# hump.net
KiCad netlist of a schematic drawn in EAGLE
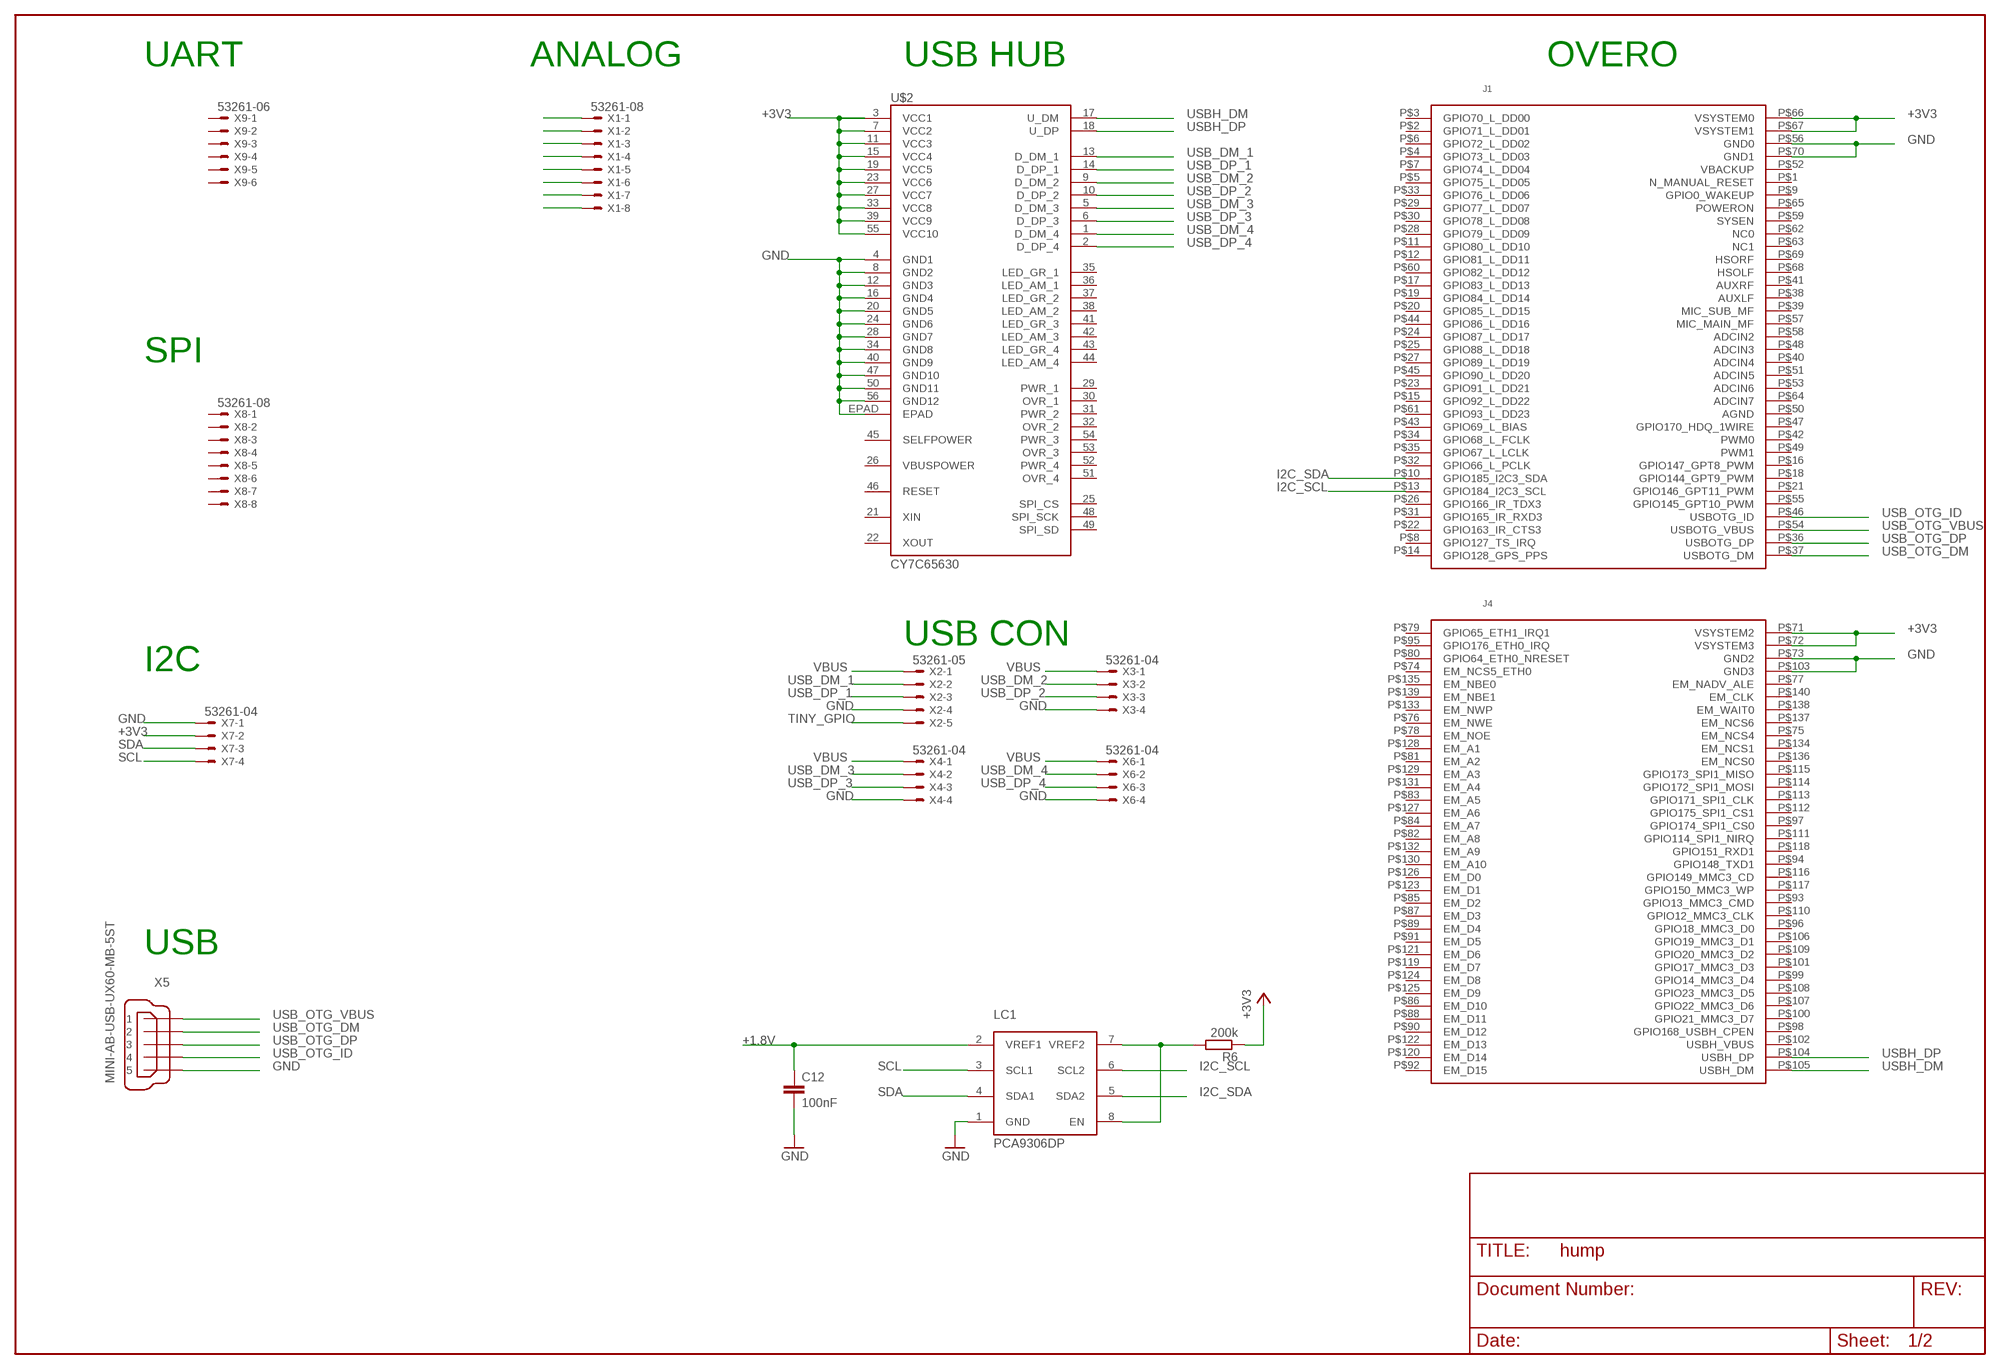
[diagram p0: schematic, sheet 1]
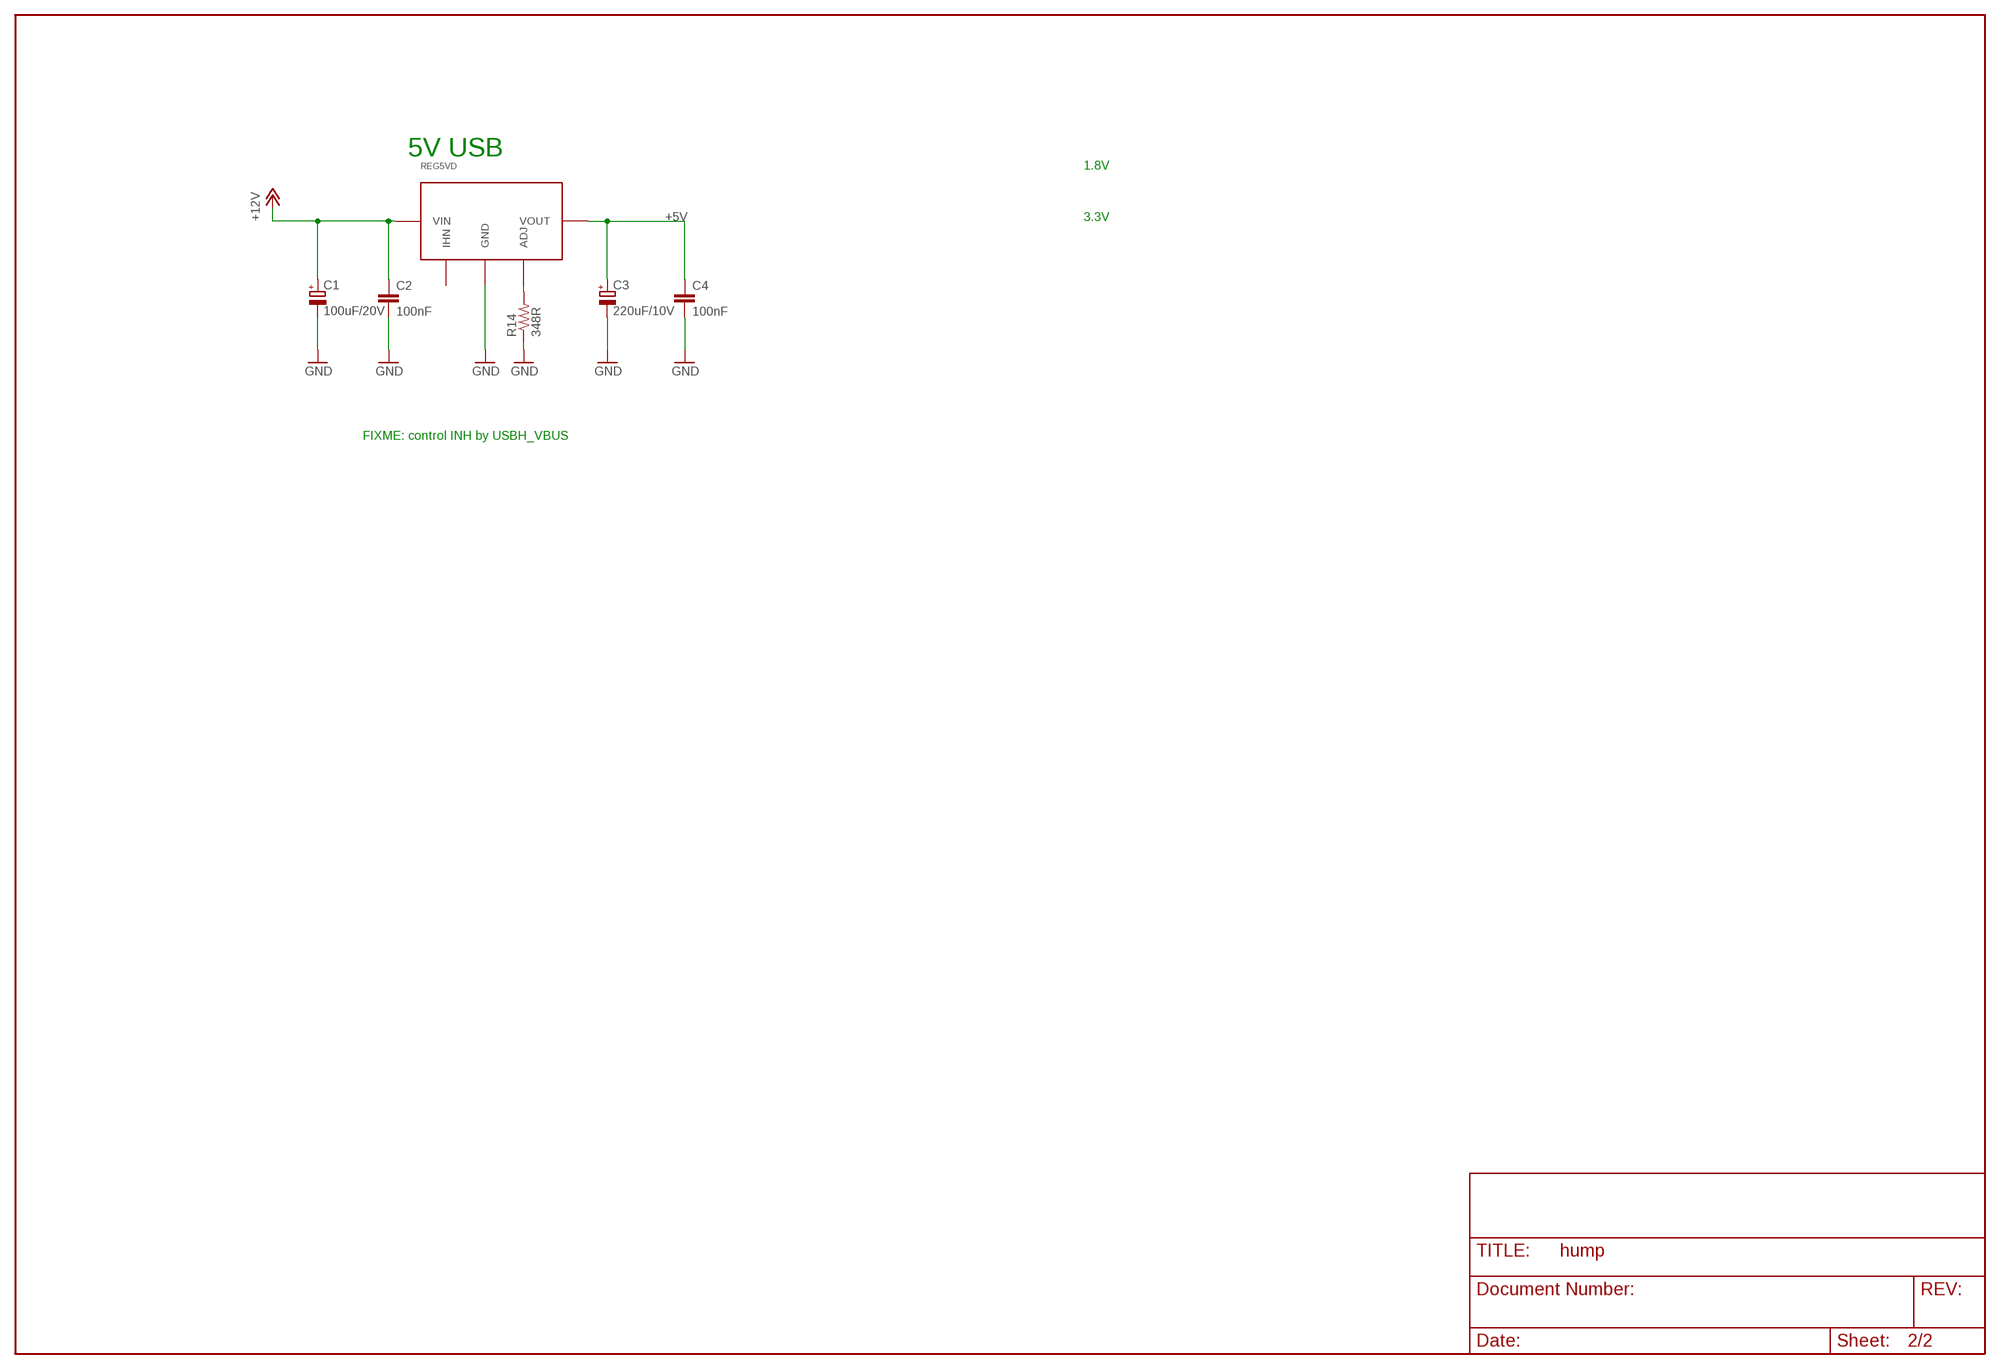
[diagram p1: schematic, sheet 2]

(export (version "E")
  (design (tool "Eeschema 10.0.6"))
  (components
    (comp (ref "C12")
      (value "100nF")
      (footprint "eagle-import:C0603")
      (libsource (lib "eagle-import") (part "C-EUC0603"))
    )
    (comp (ref "LC1")
      (value "PCA9306DP")
      (footprint "eagle-import:TSSOP_B3")
      (libsource (lib "eagle-import") (part "PCA9306DP"))
    )
    (comp (ref "R6")
      (value "200k")
      (footprint "eagle-import:R0603")
      (libsource (lib "eagle-import") (part "R-EU_R0603"))
    )
    (comp (ref "U$1")
      (value "CON_OVERO")
      (footprint "eagle-import:CON_OVERO")
      (libsource (lib "eagle-import") (part "CON_OVERO"))
    )
    (comp (ref "U$2")
      (value "CY7C65630")
      (footprint "eagle-import:QFN56")
      (libsource (lib "eagle-import") (part "CY7C65630"))
    )
    (comp (ref "X1")
      (value "53261-08")
      (footprint "eagle-import:53261-08")
      (libsource (lib "eagle-import") (part "53?-08261"))
    )
    (comp (ref "X2")
      (value "53261-05")
      (footprint "eagle-import:53261-05")
      (libsource (lib "eagle-import") (part "53?-05261"))
    )
    (comp (ref "X3")
      (value "53261-04")
      (footprint "eagle-import:53261-04")
      (libsource (lib "eagle-import") (part "53?-04261"))
    )
    (comp (ref "X4")
      (value "53261-04")
      (footprint "eagle-import:53261-04")
      (libsource (lib "eagle-import") (part "53?-04261"))
    )
    (comp (ref "X5")
      (value "MINI-AB-USB-UX60-MB-5ST")
      (footprint "eagle-import:UX60-MB-5ST")
      (libsource (lib "eagle-import") (part "MINI-USB-UX60-MB-5ST"))
    )
    (comp (ref "X6")
      (value "53261-04")
      (footprint "eagle-import:53261-04")
      (libsource (lib "eagle-import") (part "53?-04261"))
    )
    (comp (ref "X7")
      (value "53261-04")
      (footprint "eagle-import:53261-04")
      (libsource (lib "eagle-import") (part "53?-04261"))
    )
    (comp (ref "X8")
      (value "53261-08")
      (footprint "eagle-import:53261-08")
      (libsource (lib "eagle-import") (part "53?-08261"))
    )
    (comp (ref "X9")
      (value "53261-06")
      (footprint "eagle-import:53261-06")
      (libsource (lib "eagle-import") (part "53?-06261"))
    )
    (comp (ref "C1")
      (value "100uF/20V")
      (footprint "eagle-import:SMC_D")
      (libsource (lib "eagle-import") (part "CPOL-EUSMCD"))
    )
    (comp (ref "C2")
      (value "100nF")
      (footprint "eagle-import:C0603")
      (libsource (lib "eagle-import") (part "C-EUC0603"))
    )
    (comp (ref "C3")
      (value "220uF/10V")
      (footprint "eagle-import:SMC_D")
      (libsource (lib "eagle-import") (part "CPOL-EUSMCD"))
    )
    (comp (ref "C4")
      (value "100nF")
      (footprint "eagle-import:C0603")
      (libsource (lib "eagle-import") (part "C-EUC0603"))
    )
    (comp (ref "R14")
      (value "348R")
      (footprint "eagle-import:R0603")
      (libsource (lib "eagle-import") (part "R-US_R0603"))
    )
    (comp (ref "REG5VD")
      (value "PTHTH")
      (footprint "eagle-import:PTH_TH")
      (libsource (lib "eagle-import") (part "PTHTH"))
    )
  )
  (nets
    (net (code "1") (name "+1.8V") (class "Default")
      (node (ref "C12") (pin "1") (pinfunction "1_1") (pintype "passive"))
      (node (ref "LC1") (pin "2") (pinfunction "VREF1_2") (pintype "bidirectional"))
    )
    (net (code "2") (name "+3V3") (class "Default")
      (node (ref "R6") (pin "1") (pinfunction "1_1") (pintype "passive"))
      (node (ref "U$1") (pin "P$66") (pinfunction "VSYSTEM0_P$66") (pintype "bidirectional"))
      (node (ref "U$1") (pin "P$67") (pinfunction "VSYSTEM1_P$67") (pintype "bidirectional"))
      (node (ref "U$1") (pin "P$71") (pinfunction "VSYSTEM2_P$71") (pintype "bidirectional"))
      (node (ref "U$1") (pin "P$72") (pinfunction "VSYSTEM3_P$72") (pintype "bidirectional"))
      (node (ref "U$2") (pin "11") (pinfunction "VCC3_11") (pintype "power_in"))
      (node (ref "U$2") (pin "15") (pinfunction "VCC4_15") (pintype "power_in"))
      (node (ref "U$2") (pin "19") (pinfunction "VCC5_19") (pintype "power_in"))
      (node (ref "U$2") (pin "23") (pinfunction "VCC6_23") (pintype "power_in"))
      (node (ref "U$2") (pin "27") (pinfunction "VCC7_27") (pintype "power_in"))
      (node (ref "U$2") (pin "3") (pinfunction "VCC1_3") (pintype "power_in"))
      (node (ref "U$2") (pin "33") (pinfunction "VCC8_33") (pintype "power_in"))
      (node (ref "U$2") (pin "39") (pinfunction "VCC9_39") (pintype "power_in"))
      (node (ref "U$2") (pin "55") (pinfunction "VCC10_55") (pintype "power_in"))
      (node (ref "U$2") (pin "7") (pinfunction "VCC2_7") (pintype "power_in"))
      (node (ref "X7") (pin "2") (pinfunction "S_2") (pintype "passive"))
    )
    (net (code "3") (name "+5V") (class "Default")
      (node (ref "C3") (pin "+") (pinfunction "+_+") (pintype "passive"))
      (node (ref "C4") (pin "1") (pinfunction "1_1") (pintype "passive"))
      (node (ref "REG5VD") (pin "P$3") (pinfunction "VOUT_P$3") (pintype "bidirectional"))
    )
    (net (code "4") (name "+12V") (class "Default")
      (node (ref "C1") (pin "+") (pinfunction "+_+") (pintype "passive"))
      (node (ref "C2") (pin "1") (pinfunction "1_1") (pintype "passive"))
      (node (ref "REG5VD") (pin "P$1") (pinfunction "VIN_P$1") (pintype "bidirectional"))
    )
    (net (code "5") (name "GND") (class "Default")
      (node (ref "C1") (pin "-") (pinfunction "-_-") (pintype "passive"))
      (node (ref "C12") (pin "2") (pinfunction "2_2") (pintype "passive"))
      (node (ref "C2") (pin "2") (pinfunction "2_2") (pintype "passive"))
      (node (ref "C3") (pin "-") (pinfunction "-_-") (pintype "passive"))
      (node (ref "C4") (pin "2") (pinfunction "2_2") (pintype "passive"))
      (node (ref "LC1") (pin "1") (pinfunction "GND_1") (pintype "bidirectional"))
      (node (ref "R14") (pin "1") (pinfunction "1_1") (pintype "passive"))
      (node (ref "REG5VD") (pin "P$2") (pinfunction "GND_P$2") (pintype "bidirectional"))
      (node (ref "U$1") (pin "P$103") (pinfunction "GND3_P$103") (pintype "bidirectional"))
      (node (ref "U$1") (pin "P$56") (pinfunction "GND0_P$56") (pintype "bidirectional"))
      (node (ref "U$1") (pin "P$70") (pinfunction "GND1_P$70") (pintype "bidirectional"))
      (node (ref "U$1") (pin "P$73") (pinfunction "GND2_P$73") (pintype "bidirectional"))
      (node (ref "U$2") (pin "12") (pinfunction "GND3_12") (pintype "power_in"))
      (node (ref "U$2") (pin "16") (pinfunction "GND4_16") (pintype "power_in"))
      (node (ref "U$2") (pin "20") (pinfunction "GND5_20") (pintype "power_in"))
      (node (ref "U$2") (pin "24") (pinfunction "GND6_24") (pintype "power_in"))
      (node (ref "U$2") (pin "28") (pinfunction "GND7_28") (pintype "power_in"))
      (node (ref "U$2") (pin "34") (pinfunction "GND8_34") (pintype "power_in"))
      (node (ref "U$2") (pin "4") (pinfunction "GND1_4") (pintype "power_in"))
      (node (ref "U$2") (pin "40") (pinfunction "GND9_40") (pintype "power_in"))
      (node (ref "U$2") (pin "47") (pinfunction "GND10_47") (pintype "power_in"))
      (node (ref "U$2") (pin "50") (pinfunction "GND11_50") (pintype "power_in"))
      (node (ref "U$2") (pin "56") (pinfunction "GND12_56") (pintype "power_in"))
      (node (ref "U$2") (pin "8") (pinfunction "GND2_8") (pintype "power_in"))
      (node (ref "U$2") (pin "EPAD") (pinfunction "EPAD_EPAD") (pintype "power_in"))
      (node (ref "X1") (pin "1") (pinfunction "S_1") (pintype "passive"))
      (node (ref "X2") (pin "4") (pinfunction "S_4") (pintype "passive"))
      (node (ref "X3") (pin "4") (pinfunction "S_4") (pintype "passive"))
      (node (ref "X4") (pin "4") (pinfunction "S_4") (pintype "passive"))
      (node (ref "X5") (pin "5") (pinfunction "5_5") (pintype "input"))
      (node (ref "X6") (pin "4") (pinfunction "S_4") (pintype "passive"))
      (node (ref "X7") (pin "1") (pinfunction "S_1") (pintype "passive"))
    )
    (net (code "6") (name "I2C_SCL") (class "Default")
      (node (ref "LC1") (pin "6") (pinfunction "SCL2_6") (pintype "bidirectional"))
      (node (ref "U$1") (pin "P$13") (pinfunction "GPIO184_I2C3_SCL_P$13") (pintype "bidirectional"))
    )
    (net (code "7") (name "I2C_SDA") (class "Default")
      (node (ref "LC1") (pin "5") (pinfunction "SDA2_5") (pintype "bidirectional"))
      (node (ref "U$1") (pin "P$10") (pinfunction "GPIO185_I2C3_SDA_P$10") (pintype "bidirectional"))
    )
    (net (code "8") (name "Net-(LC1-EN)") (class "Default")
      (node (ref "LC1") (pin "7") (pinfunction "VREF2_7") (pintype "bidirectional"))
      (node (ref "LC1") (pin "8") (pinfunction "EN_8") (pintype "bidirectional"))
      (node (ref "R6") (pin "2") (pinfunction "2_2") (pintype "passive"))
    )
    (net (code "9") (name "Net-(REG5VD-ADJ)") (class "Default")
      (node (ref "R14") (pin "2") (pinfunction "2_2") (pintype "passive"))
      (node (ref "REG5VD") (pin "P$4") (pinfunction "ADJ_P$4") (pintype "bidirectional"))
    )
    (net (code "10") (name "SCL") (class "Default")
      (node (ref "LC1") (pin "3") (pinfunction "SCL1_3") (pintype "bidirectional"))
      (node (ref "X7") (pin "4") (pinfunction "S_4") (pintype "passive"))
    )
    (net (code "11") (name "SDA") (class "Default")
      (node (ref "LC1") (pin "4") (pinfunction "SDA1_4") (pintype "bidirectional"))
      (node (ref "X7") (pin "3") (pinfunction "S_3") (pintype "passive"))
    )
    (net (code "12") (name "TINY_GPIO") (class "Default")
      (node (ref "X2") (pin "5") (pinfunction "S_5") (pintype "passive"))
    )
    (net (code "13") (name "USBH_DM") (class "Default")
      (node (ref "U$1") (pin "P$105") (pinfunction "USBH_DM_P$105") (pintype "bidirectional"))
      (node (ref "U$2") (pin "17") (pinfunction "U_DM_17") (pintype "bidirectional"))
    )
    (net (code "14") (name "USBH_DP") (class "Default")
      (node (ref "U$1") (pin "P$104") (pinfunction "USBH_DP_P$104") (pintype "bidirectional"))
      (node (ref "U$2") (pin "18") (pinfunction "U_DP_18") (pintype "bidirectional"))
    )
    (net (code "15") (name "USB_DM_1") (class "Default")
      (node (ref "U$2") (pin "13") (pinfunction "D_DM_1_13") (pintype "bidirectional"))
      (node (ref "X2") (pin "2") (pinfunction "S_2") (pintype "passive"))
    )
    (net (code "16") (name "USB_DM_2") (class "Default")
      (node (ref "U$2") (pin "9") (pinfunction "D_DM_2_9") (pintype "bidirectional"))
      (node (ref "X3") (pin "2") (pinfunction "S_2") (pintype "passive"))
    )
    (net (code "17") (name "USB_DM_3") (class "Default")
      (node (ref "U$2") (pin "5") (pinfunction "D_DM_3_5") (pintype "bidirectional"))
      (node (ref "X4") (pin "2") (pinfunction "S_2") (pintype "passive"))
    )
    (net (code "18") (name "USB_DM_4") (class "Default")
      (node (ref "U$2") (pin "1") (pinfunction "D_DM_4_1") (pintype "bidirectional"))
      (node (ref "X6") (pin "2") (pinfunction "S_2") (pintype "passive"))
    )
    (net (code "19") (name "USB_DP_1") (class "Default")
      (node (ref "U$2") (pin "14") (pinfunction "D_DP_1_14") (pintype "bidirectional"))
      (node (ref "X2") (pin "3") (pinfunction "S_3") (pintype "passive"))
    )
    (net (code "20") (name "USB_DP_2") (class "Default")
      (node (ref "U$2") (pin "10") (pinfunction "D_DP_2_10") (pintype "bidirectional"))
      (node (ref "X3") (pin "3") (pinfunction "S_3") (pintype "passive"))
    )
    (net (code "21") (name "USB_DP_3") (class "Default")
      (node (ref "U$2") (pin "6") (pinfunction "D_DP_3_6") (pintype "bidirectional"))
      (node (ref "X4") (pin "3") (pinfunction "S_3") (pintype "passive"))
    )
    (net (code "22") (name "USB_DP_4") (class "Default")
      (node (ref "U$2") (pin "2") (pinfunction "D_DP_4_2") (pintype "bidirectional"))
      (node (ref "X6") (pin "3") (pinfunction "S_3") (pintype "passive"))
    )
    (net (code "23") (name "USB_OTG_DM") (class "Default")
      (node (ref "U$1") (pin "P$37") (pinfunction "USBOTG_DM_P$37") (pintype "bidirectional"))
      (node (ref "X5") (pin "2") (pinfunction "2_2") (pintype "input"))
    )
    (net (code "24") (name "USB_OTG_DP") (class "Default")
      (node (ref "U$1") (pin "P$36") (pinfunction "USBOTG_DP_P$36") (pintype "bidirectional"))
      (node (ref "X5") (pin "3") (pinfunction "3_3") (pintype "input"))
    )
    (net (code "25") (name "USB_OTG_ID") (class "Default")
      (node (ref "U$1") (pin "P$46") (pinfunction "USBOTG_ID_P$46") (pintype "bidirectional"))
      (node (ref "X5") (pin "4") (pinfunction "4_4") (pintype "input"))
    )
    (net (code "26") (name "USB_OTG_VBUS") (class "Default")
      (node (ref "U$1") (pin "P$54") (pinfunction "USBOTG_VBUS_P$54") (pintype "bidirectional"))
      (node (ref "X5") (pin "1") (pinfunction "1_1") (pintype "input"))
    )
    (net (code "27") (name "VBUS") (class "Default")
      (node (ref "X2") (pin "1") (pinfunction "S_1") (pintype "passive"))
      (node (ref "X3") (pin "1") (pinfunction "S_1") (pintype "passive"))
      (node (ref "X4") (pin "1") (pinfunction "S_1") (pintype "passive"))
      (node (ref "X6") (pin "1") (pinfunction "S_1") (pintype "passive"))
    )
    (net (code "28") (name "unconnected-(REG5VD-IHN-PadP$5)") (class "Default")
      (node (ref "REG5VD") (pin "P$5") (pinfunction "IHN_P$5") (pintype "bidirectional"))
    )
    (net (code "29") (name "unconnected-(U$1-ADCIN2-PadP$58)") (class "Default")
      (node (ref "U$1") (pin "P$58") (pinfunction "ADCIN2_P$58") (pintype "bidirectional"))
    )
    (net (code "30") (name "unconnected-(U$1-ADCIN3-PadP$48)") (class "Default")
      (node (ref "U$1") (pin "P$48") (pinfunction "ADCIN3_P$48") (pintype "bidirectional"))
    )
    (net (code "31") (name "unconnected-(U$1-ADCIN4-PadP$40)") (class "Default")
      (node (ref "U$1") (pin "P$40") (pinfunction "ADCIN4_P$40") (pintype "bidirectional"))
    )
    (net (code "32") (name "unconnected-(U$1-ADCIN5-PadP$51)") (class "Default")
      (node (ref "U$1") (pin "P$51") (pinfunction "ADCIN5_P$51") (pintype "bidirectional"))
    )
    (net (code "33") (name "unconnected-(U$1-ADCIN6-PadP$53)") (class "Default")
      (node (ref "U$1") (pin "P$53") (pinfunction "ADCIN6_P$53") (pintype "bidirectional"))
    )
    (net (code "34") (name "unconnected-(U$1-ADCIN7-PadP$64)") (class "Default")
      (node (ref "U$1") (pin "P$64") (pinfunction "ADCIN7_P$64") (pintype "bidirectional"))
    )
    (net (code "35") (name "unconnected-(U$1-AGND-PadP$50)") (class "Default")
      (node (ref "U$1") (pin "P$50") (pinfunction "AGND_P$50") (pintype "bidirectional"))
    )
    (net (code "36") (name "unconnected-(U$1-AUXLF-PadP$38)") (class "Default")
      (node (ref "U$1") (pin "P$38") (pinfunction "AUXLF_P$38") (pintype "bidirectional"))
    )
    (net (code "37") (name "unconnected-(U$1-AUXRF-PadP$41)") (class "Default")
      (node (ref "U$1") (pin "P$41") (pinfunction "AUXRF_P$41") (pintype "bidirectional"))
    )
    (net (code "38") (name "unconnected-(U$1-EM_A1-PadP$128)") (class "Default")
      (node (ref "U$1") (pin "P$128") (pinfunction "EM_A1_P$128") (pintype "bidirectional"))
    )
    (net (code "39") (name "unconnected-(U$1-EM_A2-PadP$81)") (class "Default")
      (node (ref "U$1") (pin "P$81") (pinfunction "EM_A2_P$81") (pintype "bidirectional"))
    )
    (net (code "40") (name "unconnected-(U$1-EM_A3-PadP$129)") (class "Default")
      (node (ref "U$1") (pin "P$129") (pinfunction "EM_A3_P$129") (pintype "bidirectional"))
    )
    (net (code "41") (name "unconnected-(U$1-EM_A4-PadP$131)") (class "Default")
      (node (ref "U$1") (pin "P$131") (pinfunction "EM_A4_P$131") (pintype "bidirectional"))
    )
    (net (code "42") (name "unconnected-(U$1-EM_A5-PadP$83)") (class "Default")
      (node (ref "U$1") (pin "P$83") (pinfunction "EM_A5_P$83") (pintype "bidirectional"))
    )
    (net (code "43") (name "unconnected-(U$1-EM_A6-PadP$127)") (class "Default")
      (node (ref "U$1") (pin "P$127") (pinfunction "EM_A6_P$127") (pintype "bidirectional"))
    )
    (net (code "44") (name "unconnected-(U$1-EM_A7-PadP$84)") (class "Default")
      (node (ref "U$1") (pin "P$84") (pinfunction "EM_A7_P$84") (pintype "bidirectional"))
    )
    (net (code "45") (name "unconnected-(U$1-EM_A8-PadP$82)") (class "Default")
      (node (ref "U$1") (pin "P$82") (pinfunction "EM_A8_P$82") (pintype "bidirectional"))
    )
    (net (code "46") (name "unconnected-(U$1-EM_A9-PadP$132)") (class "Default")
      (node (ref "U$1") (pin "P$132") (pinfunction "EM_A9_P$132") (pintype "bidirectional"))
    )
    (net (code "47") (name "unconnected-(U$1-EM_A10-PadP$130)") (class "Default")
      (node (ref "U$1") (pin "P$130") (pinfunction "EM_A10_P$130") (pintype "bidirectional"))
    )
    (net (code "48") (name "unconnected-(U$1-EM_CLK-PadP$140)") (class "Default")
      (node (ref "U$1") (pin "P$140") (pinfunction "EM_CLK_P$140") (pintype "bidirectional"))
    )
    (net (code "49") (name "unconnected-(U$1-EM_D0-PadP$126)") (class "Default")
      (node (ref "U$1") (pin "P$126") (pinfunction "EM_D0_P$126") (pintype "bidirectional"))
    )
    (net (code "50") (name "unconnected-(U$1-EM_D1-PadP$123)") (class "Default")
      (node (ref "U$1") (pin "P$123") (pinfunction "EM_D1_P$123") (pintype "bidirectional"))
    )
    (net (code "51") (name "unconnected-(U$1-EM_D2-PadP$85)") (class "Default")
      (node (ref "U$1") (pin "P$85") (pinfunction "EM_D2_P$85") (pintype "bidirectional"))
    )
    (net (code "52") (name "unconnected-(U$1-EM_D3-PadP$87)") (class "Default")
      (node (ref "U$1") (pin "P$87") (pinfunction "EM_D3_P$87") (pintype "bidirectional"))
    )
    (net (code "53") (name "unconnected-(U$1-EM_D4-PadP$89)") (class "Default")
      (node (ref "U$1") (pin "P$89") (pinfunction "EM_D4_P$89") (pintype "bidirectional"))
    )
    (net (code "54") (name "unconnected-(U$1-EM_D5-PadP$91)") (class "Default")
      (node (ref "U$1") (pin "P$91") (pinfunction "EM_D5_P$91") (pintype "bidirectional"))
    )
    (net (code "55") (name "unconnected-(U$1-EM_D6-PadP$121)") (class "Default")
      (node (ref "U$1") (pin "P$121") (pinfunction "EM_D6_P$121") (pintype "bidirectional"))
    )
    (net (code "56") (name "unconnected-(U$1-EM_D7-PadP$119)") (class "Default")
      (node (ref "U$1") (pin "P$119") (pinfunction "EM_D7_P$119") (pintype "bidirectional"))
    )
    (net (code "57") (name "unconnected-(U$1-EM_D8-PadP$124)") (class "Default")
      (node (ref "U$1") (pin "P$124") (pinfunction "EM_D8_P$124") (pintype "bidirectional"))
    )
    (net (code "58") (name "unconnected-(U$1-EM_D9-PadP$125)") (class "Default")
      (node (ref "U$1") (pin "P$125") (pinfunction "EM_D9_P$125") (pintype "bidirectional"))
    )
    (net (code "59") (name "unconnected-(U$1-EM_D10-PadP$86)") (class "Default")
      (node (ref "U$1") (pin "P$86") (pinfunction "EM_D10_P$86") (pintype "bidirectional"))
    )
    (net (code "60") (name "unconnected-(U$1-EM_D11-PadP$88)") (class "Default")
      (node (ref "U$1") (pin "P$88") (pinfunction "EM_D11_P$88") (pintype "bidirectional"))
    )
    (net (code "61") (name "unconnected-(U$1-EM_D12-PadP$90)") (class "Default")
      (node (ref "U$1") (pin "P$90") (pinfunction "EM_D12_P$90") (pintype "bidirectional"))
    )
    (net (code "62") (name "unconnected-(U$1-EM_D13-PadP$122)") (class "Default")
      (node (ref "U$1") (pin "P$122") (pinfunction "EM_D13_P$122") (pintype "bidirectional"))
    )
    (net (code "63") (name "unconnected-(U$1-EM_D14-PadP$120)") (class "Default")
      (node (ref "U$1") (pin "P$120") (pinfunction "EM_D14_P$120") (pintype "bidirectional"))
    )
    (net (code "64") (name "unconnected-(U$1-EM_D15-PadP$92)") (class "Default")
      (node (ref "U$1") (pin "P$92") (pinfunction "EM_D15_P$92") (pintype "bidirectional"))
    )
    (net (code "65") (name "unconnected-(U$1-EM_NADV_ALE-PadP$77)") (class "Default")
      (node (ref "U$1") (pin "P$77") (pinfunction "EM_NADV_ALE_P$77") (pintype "bidirectional"))
    )
    (net (code "66") (name "unconnected-(U$1-EM_NBE0-PadP$135)") (class "Default")
      (node (ref "U$1") (pin "P$135") (pinfunction "EM_NBE0_P$135") (pintype "bidirectional"))
    )
    (net (code "67") (name "unconnected-(U$1-EM_NBE1-PadP$139)") (class "Default")
      (node (ref "U$1") (pin "P$139") (pinfunction "EM_NBE1_P$139") (pintype "bidirectional"))
    )
    (net (code "68") (name "unconnected-(U$1-EM_NCS0-PadP$136)") (class "Default")
      (node (ref "U$1") (pin "P$136") (pinfunction "EM_NCS0_P$136") (pintype "bidirectional"))
    )
    (net (code "69") (name "unconnected-(U$1-EM_NCS1-PadP$134)") (class "Default")
      (node (ref "U$1") (pin "P$134") (pinfunction "EM_NCS1_P$134") (pintype "bidirectional"))
    )
    (net (code "70") (name "unconnected-(U$1-EM_NCS4-PadP$75)") (class "Default")
      (node (ref "U$1") (pin "P$75") (pinfunction "EM_NCS4_P$75") (pintype "bidirectional"))
    )
    (net (code "71") (name "unconnected-(U$1-EM_NCS5_ETH0-PadP$74)") (class "Default")
      (node (ref "U$1") (pin "P$74") (pinfunction "EM_NCS5_ETH0_P$74") (pintype "bidirectional"))
    )
    (net (code "72") (name "unconnected-(U$1-EM_NCS6-PadP$137)") (class "Default")
      (node (ref "U$1") (pin "P$137") (pinfunction "EM_NCS6_P$137") (pintype "bidirectional"))
    )
    (net (code "73") (name "unconnected-(U$1-EM_NOE-PadP$78)") (class "Default")
      (node (ref "U$1") (pin "P$78") (pinfunction "EM_NOE_P$78") (pintype "bidirectional"))
    )
    (net (code "74") (name "unconnected-(U$1-EM_NWE-PadP$76)") (class "Default")
      (node (ref "U$1") (pin "P$76") (pinfunction "EM_NWE_P$76") (pintype "bidirectional"))
    )
    (net (code "75") (name "unconnected-(U$1-EM_NWP-PadP$133)") (class "Default")
      (node (ref "U$1") (pin "P$133") (pinfunction "EM_NWP_P$133") (pintype "bidirectional"))
    )
    (net (code "76") (name "unconnected-(U$1-EM_WAIT0-PadP$138)") (class "Default")
      (node (ref "U$1") (pin "P$138") (pinfunction "EM_WAIT0_P$138") (pintype "bidirectional"))
    )
    (net (code "77") (name "unconnected-(U$1-GPIO0_WAKEUP-PadP$9)") (class "Default")
      (node (ref "U$1") (pin "P$9") (pinfunction "GPIO0_WAKEUP_P$9") (pintype "bidirectional"))
    )
    (net (code "78") (name "unconnected-(U$1-GPIO12_MMC3_CLK-PadP$110)") (class "Default")
      (node (ref "U$1") (pin "P$110") (pinfunction "GPIO12_MMC3_CLK_P$110") (pintype "bidirectional"))
    )
    (net (code "79") (name "unconnected-(U$1-GPIO13_MMC3_CMD-PadP$93)") (class "Default")
      (node (ref "U$1") (pin "P$93") (pinfunction "GPIO13_MMC3_CMD_P$93") (pintype "bidirectional"))
    )
    (net (code "80") (name "unconnected-(U$1-GPIO14_MMC3_D4-PadP$99)") (class "Default")
      (node (ref "U$1") (pin "P$99") (pinfunction "GPIO14_MMC3_D4_P$99") (pintype "bidirectional"))
    )
    (net (code "81") (name "unconnected-(U$1-GPIO17_MMC3_D3-PadP$101)") (class "Default")
      (node (ref "U$1") (pin "P$101") (pinfunction "GPIO17_MMC3_D3_P$101") (pintype "bidirectional"))
    )
    (net (code "82") (name "unconnected-(U$1-GPIO18_MMC3_D0-PadP$96)") (class "Default")
      (node (ref "U$1") (pin "P$96") (pinfunction "GPIO18_MMC3_D0_P$96") (pintype "bidirectional"))
    )
    (net (code "83") (name "unconnected-(U$1-GPIO19_MMC3_D1-PadP$106)") (class "Default")
      (node (ref "U$1") (pin "P$106") (pinfunction "GPIO19_MMC3_D1_P$106") (pintype "bidirectional"))
    )
    (net (code "84") (name "unconnected-(U$1-GPIO20_MMC3_D2-PadP$109)") (class "Default")
      (node (ref "U$1") (pin "P$109") (pinfunction "GPIO20_MMC3_D2_P$109") (pintype "bidirectional"))
    )
    (net (code "85") (name "unconnected-(U$1-GPIO21_MMC3_D7-PadP$100)") (class "Default")
      (node (ref "U$1") (pin "P$100") (pinfunction "GPIO21_MMC3_D7_P$100") (pintype "bidirectional"))
    )
    (net (code "86") (name "unconnected-(U$1-GPIO22_MMC3_D6-PadP$107)") (class "Default")
      (node (ref "U$1") (pin "P$107") (pinfunction "GPIO22_MMC3_D6_P$107") (pintype "bidirectional"))
    )
    (net (code "87") (name "unconnected-(U$1-GPIO23_MMC3_D5-PadP$108)") (class "Default")
      (node (ref "U$1") (pin "P$108") (pinfunction "GPIO23_MMC3_D5_P$108") (pintype "bidirectional"))
    )
    (net (code "88") (name "unconnected-(U$1-GPIO64_ETH0_NRESET-PadP$80)") (class "Default")
      (node (ref "U$1") (pin "P$80") (pinfunction "GPIO64_ETH0_NRESET_P$80") (pintype "bidirectional"))
    )
    (net (code "89") (name "unconnected-(U$1-GPIO65_ETH1_IRQ1-PadP$79)") (class "Default")
      (node (ref "U$1") (pin "P$79") (pinfunction "GPIO65_ETH1_IRQ1_P$79") (pintype "bidirectional"))
    )
    (net (code "90") (name "unconnected-(U$1-GPIO66_L_PCLK-PadP$32)") (class "Default")
      (node (ref "U$1") (pin "P$32") (pinfunction "GPIO66_L_PCLK_P$32") (pintype "bidirectional"))
    )
    (net (code "91") (name "unconnected-(U$1-GPIO67_L_LCLK-PadP$35)") (class "Default")
      (node (ref "U$1") (pin "P$35") (pinfunction "GPIO67_L_LCLK_P$35") (pintype "bidirectional"))
    )
    (net (code "92") (name "unconnected-(U$1-GPIO68_L_FCLK-PadP$34)") (class "Default")
      (node (ref "U$1") (pin "P$34") (pinfunction "GPIO68_L_FCLK_P$34") (pintype "bidirectional"))
    )
    (net (code "93") (name "unconnected-(U$1-GPIO69_L_BIAS-PadP$43)") (class "Default")
      (node (ref "U$1") (pin "P$43") (pinfunction "GPIO69_L_BIAS_P$43") (pintype "bidirectional"))
    )
    (net (code "94") (name "unconnected-(U$1-GPIO70_L_DD00-PadP$3)") (class "Default")
      (node (ref "U$1") (pin "P$3") (pinfunction "GPIO70_L_DD00_P$3") (pintype "bidirectional"))
    )
    (net (code "95") (name "unconnected-(U$1-GPIO71_L_DD01-PadP$2)") (class "Default")
      (node (ref "U$1") (pin "P$2") (pinfunction "GPIO71_L_DD01_P$2") (pintype "bidirectional"))
    )
    (net (code "96") (name "unconnected-(U$1-GPIO72_L_DD02-PadP$6)") (class "Default")
      (node (ref "U$1") (pin "P$6") (pinfunction "GPIO72_L_DD02_P$6") (pintype "bidirectional"))
    )
    (net (code "97") (name "unconnected-(U$1-GPIO73_L_DD03-PadP$4)") (class "Default")
      (node (ref "U$1") (pin "P$4") (pinfunction "GPIO73_L_DD03_P$4") (pintype "bidirectional"))
    )
    (net (code "98") (name "unconnected-(U$1-GPIO74_L_DD04-PadP$7)") (class "Default")
      (node (ref "U$1") (pin "P$7") (pinfunction "GPIO74_L_DD04_P$7") (pintype "bidirectional"))
    )
    (net (code "99") (name "unconnected-(U$1-GPIO75_L_DD05-PadP$5)") (class "Default")
      (node (ref "U$1") (pin "P$5") (pinfunction "GPIO75_L_DD05_P$5") (pintype "bidirectional"))
    )
    (net (code "100") (name "unconnected-(U$1-GPIO76_L_DD06-PadP$33)") (class "Default")
      (node (ref "U$1") (pin "P$33") (pinfunction "GPIO76_L_DD06_P$33") (pintype "bidirectional"))
    )
    (net (code "101") (name "unconnected-(U$1-GPIO77_L_DD07-PadP$29)") (class "Default")
      (node (ref "U$1") (pin "P$29") (pinfunction "GPIO77_L_DD07_P$29") (pintype "bidirectional"))
    )
    (net (code "102") (name "unconnected-(U$1-GPIO78_L_DD08-PadP$30)") (class "Default")
      (node (ref "U$1") (pin "P$30") (pinfunction "GPIO78_L_DD08_P$30") (pintype "bidirectional"))
    )
    (net (code "103") (name "unconnected-(U$1-GPIO79_L_DD09-PadP$28)") (class "Default")
      (node (ref "U$1") (pin "P$28") (pinfunction "GPIO79_L_DD09_P$28") (pintype "bidirectional"))
    )
    (net (code "104") (name "unconnected-(U$1-GPIO80_L_DD10-PadP$11)") (class "Default")
      (node (ref "U$1") (pin "P$11") (pinfunction "GPIO80_L_DD10_P$11") (pintype "bidirectional"))
    )
    (net (code "105") (name "unconnected-(U$1-GPIO81_L_DD11-PadP$12)") (class "Default")
      (node (ref "U$1") (pin "P$12") (pinfunction "GPIO81_L_DD11_P$12") (pintype "bidirectional"))
    )
    (net (code "106") (name "unconnected-(U$1-GPIO82_L_DD12-PadP$60)") (class "Default")
      (node (ref "U$1") (pin "P$60") (pinfunction "GPIO82_L_DD12_P$60") (pintype "bidirectional"))
    )
    (net (code "107") (name "unconnected-(U$1-GPIO83_L_DD13-PadP$17)") (class "Default")
      (node (ref "U$1") (pin "P$17") (pinfunction "GPIO83_L_DD13_P$17") (pintype "bidirectional"))
    )
    (net (code "108") (name "unconnected-(U$1-GPIO84_L_DD14-PadP$19)") (class "Default")
      (node (ref "U$1") (pin "P$19") (pinfunction "GPIO84_L_DD14_P$19") (pintype "bidirectional"))
    )
    (net (code "109") (name "unconnected-(U$1-GPIO85_L_DD15-PadP$20)") (class "Default")
      (node (ref "U$1") (pin "P$20") (pinfunction "GPIO85_L_DD15_P$20") (pintype "bidirectional"))
    )
    (net (code "110") (name "unconnected-(U$1-GPIO86_L_DD16-PadP$44)") (class "Default")
      (node (ref "U$1") (pin "P$44") (pinfunction "GPIO86_L_DD16_P$44") (pintype "bidirectional"))
    )
    (net (code "111") (name "unconnected-(U$1-GPIO87_L_DD17-PadP$24)") (class "Default")
      (node (ref "U$1") (pin "P$24") (pinfunction "GPIO87_L_DD17_P$24") (pintype "bidirectional"))
    )
    (net (code "112") (name "unconnected-(U$1-GPIO88_L_DD18-PadP$25)") (class "Default")
      (node (ref "U$1") (pin "P$25") (pinfunction "GPIO88_L_DD18_P$25") (pintype "bidirectional"))
    )
    (net (code "113") (name "unconnected-(U$1-GPIO89_L_DD19-PadP$27)") (class "Default")
      (node (ref "U$1") (pin "P$27") (pinfunction "GPIO89_L_DD19_P$27") (pintype "bidirectional"))
    )
    (net (code "114") (name "unconnected-(U$1-GPIO90_L_DD20-PadP$45)") (class "Default")
      (node (ref "U$1") (pin "P$45") (pinfunction "GPIO90_L_DD20_P$45") (pintype "bidirectional"))
    )
    (net (code "115") (name "unconnected-(U$1-GPIO91_L_DD21-PadP$23)") (class "Default")
      (node (ref "U$1") (pin "P$23") (pinfunction "GPIO91_L_DD21_P$23") (pintype "bidirectional"))
    )
    (net (code "116") (name "unconnected-(U$1-GPIO92_L_DD22-PadP$15)") (class "Default")
      (node (ref "U$1") (pin "P$15") (pinfunction "GPIO92_L_DD22_P$15") (pintype "bidirectional"))
    )
    (net (code "117") (name "unconnected-(U$1-GPIO93_L_DD23-PadP$61)") (class "Default")
      (node (ref "U$1") (pin "P$61") (pinfunction "GPIO93_L_DD23_P$61") (pintype "bidirectional"))
    )
    (net (code "118") (name "unconnected-(U$1-GPIO114_SPI1_NIRQ-PadP$111)") (class "Default")
      (node (ref "U$1") (pin "P$111") (pinfunction "GPIO114_SPI1_NIRQ_P$111") (pintype "bidirectional"))
    )
    (net (code "119") (name "unconnected-(U$1-GPIO127_TS_IRQ-PadP$8)") (class "Default")
      (node (ref "U$1") (pin "P$8") (pinfunction "GPIO127_TS_IRQ_P$8") (pintype "bidirectional"))
    )
    (net (code "120") (name "unconnected-(U$1-GPIO128_GPS_PPS-PadP$14)") (class "Default")
      (node (ref "U$1") (pin "P$14") (pinfunction "GPIO128_GPS_PPS_P$14") (pintype "bidirectional"))
    )
    (net (code "121") (name "unconnected-(U$1-GPIO144_GPT9_PWM-PadP$18)") (class "Default")
      (node (ref "U$1") (pin "P$18") (pinfunction "GPIO144_GPT9_PWM_P$18") (pintype "bidirectional"))
    )
    (net (code "122") (name "unconnected-(U$1-GPIO145_GPT10_PWM-PadP$55)") (class "Default")
      (node (ref "U$1") (pin "P$55") (pinfunction "GPIO145_GPT10_PWM_P$55") (pintype "bidirectional"))
    )
    (net (code "123") (name "unconnected-(U$1-GPIO146_GPT11_PWM-PadP$21)") (class "Default")
      (node (ref "U$1") (pin "P$21") (pinfunction "GPIO146_GPT11_PWM_P$21") (pintype "bidirectional"))
    )
    (net (code "124") (name "unconnected-(U$1-GPIO147_GPT8_PWM-PadP$16)") (class "Default")
      (node (ref "U$1") (pin "P$16") (pinfunction "GPIO147_GPT8_PWM_P$16") (pintype "bidirectional"))
    )
    (net (code "125") (name "unconnected-(U$1-GPIO148_TXD1-PadP$94)") (class "Default")
      (node (ref "U$1") (pin "P$94") (pinfunction "GPIO148_TXD1_P$94") (pintype "bidirectional"))
    )
    (net (code "126") (name "unconnected-(U$1-GPIO149_MMC3_CD-PadP$116)") (class "Default")
      (node (ref "U$1") (pin "P$116") (pinfunction "GPIO149_MMC3_CD_P$116") (pintype "bidirectional"))
    )
    (net (code "127") (name "unconnected-(U$1-GPIO150_MMC3_WP-PadP$117)") (class "Default")
      (node (ref "U$1") (pin "P$117") (pinfunction "GPIO150_MMC3_WP_P$117") (pintype "bidirectional"))
    )
    (net (code "128") (name "unconnected-(U$1-GPIO151_RXD1-PadP$118)") (class "Default")
      (node (ref "U$1") (pin "P$118") (pinfunction "GPIO151_RXD1_P$118") (pintype "bidirectional"))
    )
    (net (code "129") (name "unconnected-(U$1-GPIO163_IR_CTS3-PadP$22)") (class "Default")
      (node (ref "U$1") (pin "P$22") (pinfunction "GPIO163_IR_CTS3_P$22") (pintype "bidirectional"))
    )
    (net (code "130") (name "unconnected-(U$1-GPIO165_IR_RXD3-PadP$31)") (class "Default")
      (node (ref "U$1") (pin "P$31") (pinfunction "GPIO165_IR_RXD3_P$31") (pintype "bidirectional"))
    )
    (net (code "131") (name "unconnected-(U$1-GPIO166_IR_TDX3-PadP$26)") (class "Default")
      (node (ref "U$1") (pin "P$26") (pinfunction "GPIO166_IR_TDX3_P$26") (pintype "bidirectional"))
    )
    (net (code "132") (name "unconnected-(U$1-GPIO168_USBH_CPEN-PadP$98)") (class "Default")
      (node (ref "U$1") (pin "P$98") (pinfunction "GPIO168_USBH_CPEN_P$98") (pintype "bidirectional"))
    )
    (net (code "133") (name "unconnected-(U$1-GPIO170_HDQ_1WIRE-PadP$47)") (class "Default")
      (node (ref "U$1") (pin "P$47") (pinfunction "GPIO170_HDQ_1WIRE_P$47") (pintype "bidirectional"))
    )
    (net (code "134") (name "unconnected-(U$1-GPIO171_SPI1_CLK-PadP$113)") (class "Default")
      (node (ref "U$1") (pin "P$113") (pinfunction "GPIO171_SPI1_CLK_P$113") (pintype "bidirectional"))
    )
    (net (code "135") (name "unconnected-(U$1-GPIO172_SPI1_MOSI-PadP$114)") (class "Default")
      (node (ref "U$1") (pin "P$114") (pinfunction "GPIO172_SPI1_MOSI_P$114") (pintype "bidirectional"))
    )
    (net (code "136") (name "unconnected-(U$1-GPIO173_SPI1_MISO-PadP$115)") (class "Default")
      (node (ref "U$1") (pin "P$115") (pinfunction "GPIO173_SPI1_MISO_P$115") (pintype "bidirectional"))
    )
    (net (code "137") (name "unconnected-(U$1-GPIO174_SPI1_CS0-PadP$97)") (class "Default")
      (node (ref "U$1") (pin "P$97") (pinfunction "GPIO174_SPI1_CS0_P$97") (pintype "bidirectional"))
    )
    (net (code "138") (name "unconnected-(U$1-GPIO175_SPI1_CS1-PadP$112)") (class "Default")
      (node (ref "U$1") (pin "P$112") (pinfunction "GPIO175_SPI1_CS1_P$112") (pintype "bidirectional"))
    )
    (net (code "139") (name "unconnected-(U$1-GPIO176_ETH0_IRQ-PadP$95)") (class "Default")
      (node (ref "U$1") (pin "P$95") (pinfunction "GPIO176_ETH0_IRQ_P$95") (pintype "bidirectional"))
    )
    (net (code "140") (name "unconnected-(U$1-HSOLF-PadP$68)") (class "Default")
      (node (ref "U$1") (pin "P$68") (pinfunction "HSOLF_P$68") (pintype "bidirectional"))
    )
    (net (code "141") (name "unconnected-(U$1-HSORF-PadP$69)") (class "Default")
      (node (ref "U$1") (pin "P$69") (pinfunction "HSORF_P$69") (pintype "bidirectional"))
    )
    (net (code "142") (name "unconnected-(U$1-MIC_MAIN_MF-PadP$57)") (class "Default")
      (node (ref "U$1") (pin "P$57") (pinfunction "MIC_MAIN_MF_P$57") (pintype "bidirectional"))
    )
    (net (code "143") (name "unconnected-(U$1-MIC_SUB_MF-PadP$39)") (class "Default")
      (node (ref "U$1") (pin "P$39") (pinfunction "MIC_SUB_MF_P$39") (pintype "bidirectional"))
    )
    (net (code "144") (name "unconnected-(U$1-NC0-PadP$62)") (class "Default")
      (node (ref "U$1") (pin "P$62") (pinfunction "NC0_P$62") (pintype "bidirectional"))
    )
    (net (code "145") (name "unconnected-(U$1-NC1-PadP$63)") (class "Default")
      (node (ref "U$1") (pin "P$63") (pinfunction "NC1_P$63") (pintype "bidirectional"))
    )
    (net (code "146") (name "unconnected-(U$1-N_MANUAL_RESET-PadP$1)") (class "Default")
      (node (ref "U$1") (pin "P$1") (pinfunction "N_MANUAL_RESET_P$1") (pintype "bidirectional"))
    )
    (net (code "147") (name "unconnected-(U$1-POWERON-PadP$65)") (class "Default")
      (node (ref "U$1") (pin "P$65") (pinfunction "POWERON_P$65") (pintype "bidirectional"))
    )
    (net (code "148") (name "unconnected-(U$1-PWM0-PadP$42)") (class "Default")
      (node (ref "U$1") (pin "P$42") (pinfunction "PWM0_P$42") (pintype "bidirectional"))
    )
    (net (code "149") (name "unconnected-(U$1-PWM1-PadP$49)") (class "Default")
      (node (ref "U$1") (pin "P$49") (pinfunction "PWM1_P$49") (pintype "bidirectional"))
    )
    (net (code "150") (name "unconnected-(U$1-SYSEN-PadP$59)") (class "Default")
      (node (ref "U$1") (pin "P$59") (pinfunction "SYSEN_P$59") (pintype "bidirectional"))
    )
    (net (code "151") (name "unconnected-(U$1-USBH_VBUS-PadP$102)") (class "Default")
      (node (ref "U$1") (pin "P$102") (pinfunction "USBH_VBUS_P$102") (pintype "bidirectional"))
    )
    (net (code "152") (name "unconnected-(U$1-VBACKUP-PadP$52)") (class "Default")
      (node (ref "U$1") (pin "P$52") (pinfunction "VBACKUP_P$52") (pintype "bidirectional"))
    )
    (net (code "153") (name "unconnected-(U$2-LED_AM_1-Pad36)") (class "Default")
      (node (ref "U$2") (pin "36") (pinfunction "LED_AM_1_36") (pintype "output"))
    )
    (net (code "154") (name "unconnected-(U$2-LED_AM_2-Pad38)") (class "Default")
      (node (ref "U$2") (pin "38") (pinfunction "LED_AM_2_38") (pintype "output"))
    )
    (net (code "155") (name "unconnected-(U$2-LED_AM_3-Pad42)") (class "Default")
      (node (ref "U$2") (pin "42") (pinfunction "LED_AM_3_42") (pintype "output"))
    )
    (net (code "156") (name "unconnected-(U$2-LED_AM_4-Pad44)") (class "Default")
      (node (ref "U$2") (pin "44") (pinfunction "LED_AM_4_44") (pintype "output"))
    )
    (net (code "157") (name "unconnected-(U$2-LED_GR_1-Pad35)") (class "Default")
      (node (ref "U$2") (pin "35") (pinfunction "LED_GR_1_35") (pintype "output"))
    )
    (net (code "158") (name "unconnected-(U$2-LED_GR_2-Pad37)") (class "Default")
      (node (ref "U$2") (pin "37") (pinfunction "LED_GR_2_37") (pintype "output"))
    )
    (net (code "159") (name "unconnected-(U$2-LED_GR_3-Pad41)") (class "Default")
      (node (ref "U$2") (pin "41") (pinfunction "LED_GR_3_41") (pintype "output"))
    )
    (net (code "160") (name "unconnected-(U$2-LED_GR_4-Pad43)") (class "Default")
      (node (ref "U$2") (pin "43") (pinfunction "LED_GR_4_43") (pintype "output"))
    )
    (net (code "161") (name "unconnected-(U$2-OVR_1-Pad30)") (class "Default")
      (node (ref "U$2") (pin "30") (pinfunction "OVR_1_30") (pintype "input"))
    )
    (net (code "162") (name "unconnected-(U$2-OVR_2-Pad32)") (class "Default")
      (node (ref "U$2") (pin "32") (pinfunction "OVR_2_32") (pintype "input"))
    )
    (net (code "163") (name "unconnected-(U$2-OVR_3-Pad53)") (class "Default")
      (node (ref "U$2") (pin "53") (pinfunction "OVR_3_53") (pintype "input"))
    )
    (net (code "164") (name "unconnected-(U$2-OVR_4-Pad51)") (class "Default")
      (node (ref "U$2") (pin "51") (pinfunction "OVR_4_51") (pintype "input"))
    )
    (net (code "165") (name "unconnected-(U$2-PWR_1-Pad29)") (class "Default")
      (node (ref "U$2") (pin "29") (pinfunction "PWR_1_29") (pintype "output"))
    )
    (net (code "166") (name "unconnected-(U$2-PWR_2-Pad31)") (class "Default")
      (node (ref "U$2") (pin "31") (pinfunction "PWR_2_31") (pintype "output"))
    )
    (net (code "167") (name "unconnected-(U$2-PWR_3-Pad54)") (class "Default")
      (node (ref "U$2") (pin "54") (pinfunction "PWR_3_54") (pintype "output"))
    )
    (net (code "168") (name "unconnected-(U$2-PWR_4-Pad52)") (class "Default")
      (node (ref "U$2") (pin "52") (pinfunction "PWR_4_52") (pintype "output"))
    )
    (net (code "169") (name "unconnected-(U$2-RESET-Pad46)") (class "Default")
      (node (ref "U$2") (pin "46") (pinfunction "RESET_46") (pintype "input"))
    )
    (net (code "170") (name "unconnected-(U$2-SELFPOWER-Pad45)") (class "Default")
      (node (ref "U$2") (pin "45") (pinfunction "SELFPOWER_45") (pintype "input"))
    )
    (net (code "171") (name "unconnected-(U$2-SPI_CS-Pad25)") (class "Default")
      (node (ref "U$2") (pin "25") (pinfunction "SPI_CS_25") (pintype "output"))
    )
    (net (code "172") (name "unconnected-(U$2-SPI_SCK-Pad48)") (class "Default")
      (node (ref "U$2") (pin "48") (pinfunction "SPI_SCK_48") (pintype "output"))
    )
    (net (code "173") (name "unconnected-(U$2-SPI_SD-Pad49)") (class "Default")
      (node (ref "U$2") (pin "49") (pinfunction "SPI_SD_49") (pintype "bidirectional"))
    )
    (net (code "174") (name "unconnected-(U$2-VBUSPOWER-Pad26)") (class "Default")
      (node (ref "U$2") (pin "26") (pinfunction "VBUSPOWER_26") (pintype "input"))
    )
    (net (code "175") (name "unconnected-(U$2-XIN-Pad21)") (class "Default")
      (node (ref "U$2") (pin "21") (pinfunction "XIN_21") (pintype "input"))
    )
    (net (code "176") (name "unconnected-(U$2-XOUT-Pad22)") (class "Default")
      (node (ref "U$2") (pin "22") (pinfunction "XOUT_22") (pintype "output"))
    )
    (net (code "177") (name "unconnected-(X1B-S-Pad2)") (class "Default")
      (node (ref "X1") (pin "2") (pinfunction "S_2") (pintype "passive"))
    )
    (net (code "178") (name "unconnected-(X1C-S-Pad3)") (class "Default")
      (node (ref "X1") (pin "3") (pinfunction "S_3") (pintype "passive"))
    )
    (net (code "179") (name "unconnected-(X1D-S-Pad4)") (class "Default")
      (node (ref "X1") (pin "4") (pinfunction "S_4") (pintype "passive"))
    )
    (net (code "180") (name "unconnected-(X1E-S-Pad5)") (class "Default")
      (node (ref "X1") (pin "5") (pinfunction "S_5") (pintype "passive"))
    )
    (net (code "181") (name "unconnected-(X1F-S-Pad6)") (class "Default")
      (node (ref "X1") (pin "6") (pinfunction "S_6") (pintype "passive"))
    )
    (net (code "182") (name "unconnected-(X1G-S-Pad7)") (class "Default")
      (node (ref "X1") (pin "7") (pinfunction "S_7") (pintype "passive"))
    )
    (net (code "183") (name "unconnected-(X1H-S-Pad8)") (class "Default")
      (node (ref "X1") (pin "8") (pinfunction "S_8") (pintype "passive"))
    )
    (net (code "184") (name "unconnected-(X8A-S-Pad1)") (class "Default")
      (node (ref "X8") (pin "1") (pinfunction "S_1") (pintype "passive"))
    )
    (net (code "185") (name "unconnected-(X8B-S-Pad2)") (class "Default")
      (node (ref "X8") (pin "2") (pinfunction "S_2") (pintype "passive"))
    )
    (net (code "186") (name "unconnected-(X8C-S-Pad3)") (class "Default")
      (node (ref "X8") (pin "3") (pinfunction "S_3") (pintype "passive"))
    )
    (net (code "187") (name "unconnected-(X8D-S-Pad4)") (class "Default")
      (node (ref "X8") (pin "4") (pinfunction "S_4") (pintype "passive"))
    )
    (net (code "188") (name "unconnected-(X8E-S-Pad5)") (class "Default")
      (node (ref "X8") (pin "5") (pinfunction "S_5") (pintype "passive"))
    )
    (net (code "189") (name "unconnected-(X8F-S-Pad6)") (class "Default")
      (node (ref "X8") (pin "6") (pinfunction "S_6") (pintype "passive"))
    )
    (net (code "190") (name "unconnected-(X8G-S-Pad7)") (class "Default")
      (node (ref "X8") (pin "7") (pinfunction "S_7") (pintype "passive"))
    )
    (net (code "191") (name "unconnected-(X8H-S-Pad8)") (class "Default")
      (node (ref "X8") (pin "8") (pinfunction "S_8") (pintype "passive"))
    )
    (net (code "192") (name "unconnected-(X9A-S-Pad1)") (class "Default")
      (node (ref "X9") (pin "1") (pinfunction "S_1") (pintype "passive"))
    )
    (net (code "193") (name "unconnected-(X9B-S-Pad2)") (class "Default")
      (node (ref "X9") (pin "2") (pinfunction "S_2") (pintype "passive"))
    )
    (net (code "194") (name "unconnected-(X9C-S-Pad3)") (class "Default")
      (node (ref "X9") (pin "3") (pinfunction "S_3") (pintype "passive"))
    )
    (net (code "195") (name "unconnected-(X9D-S-Pad4)") (class "Default")
      (node (ref "X9") (pin "4") (pinfunction "S_4") (pintype "passive"))
    )
    (net (code "196") (name "unconnected-(X9E-S-Pad5)") (class "Default")
      (node (ref "X9") (pin "5") (pinfunction "S_5") (pintype "passive"))
    )
    (net (code "197") (name "unconnected-(X9F-S-Pad6)") (class "Default")
      (node (ref "X9") (pin "6") (pinfunction "S_6") (pintype "passive"))
    )
  )
)
